# LEDBAKL_TPS61042.net
KiCad netlist of a schematic drawn in Altium Designer
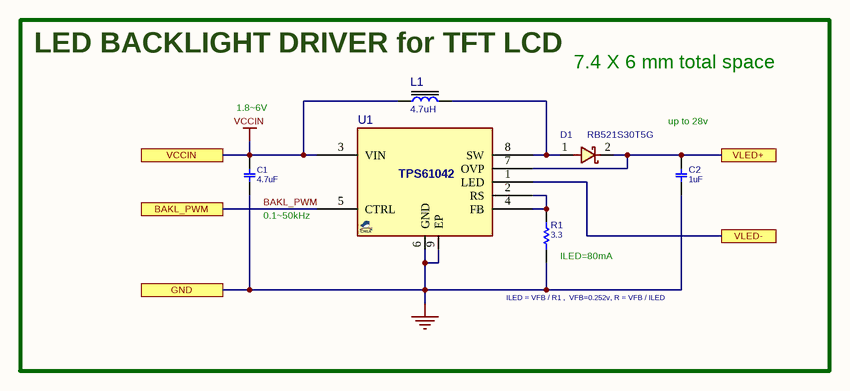
[diagram p0: LEDBAKL_TPS61042.SchDoc]

(export (version "E")
  (design (tool "Eeschema 10.0.6"))
  (components
    (comp (ref "C1")
      (value "4.7uF")
      (footprint "C0402")
      (description "CAP, MLCC")
      (fields (field (name "MANF_P#") "CL05A475MP5NRNC") (field (name "MANF") "Samsung"))
      (libsource (lib "passive_smd") (part "CAP_SMD_MLCC"))
    )
    (comp (ref "C2")
      (value "1uF")
      (footprint "C0603")
      (description "CAP, MLCC")
      (fields (field (name "MANF_P#") "CL10A105KB8NNNC") (field (name "MANF") "Samsung"))
      (libsource (lib "passive_smd") (part "CAP_SMD_MLCC"))
    )
    (comp (ref "D1")
      (value "RB521S30T5G")
      (footprint "D_SOD523")
      (description "DIODE, SCHOTTKY")
      (fields (field (name "MANF") "DIODES"))
      (libsource (lib "diode") (part "DIODE_SMD_SCHOTTKY_1N5819"))
    )
    (comp (ref "L1")
      (value "4.7uH")
      (footprint "L0603")
      (description "INDUCTOR, POWER, SMD")
      (fields (field (name "MANF_P#") "MLZ1608E4R7MT"))
      (libsource (lib "passive") (part "INDPWR_SMD"))
    )
    (comp (ref "R1")
      (value "3.3")
      (footprint "R0402")
      (description "RESISTOR, SMD, 20K, 0402")
      (fields (field (name "MANF") "Yageo") (field (name "MANF_P#") "RK73H1ETTP2002F"))
      (libsource (lib "chila_passive") (part "RES_SMD"))
    )
    (comp (ref "U1")
      (value "TPS61042")
      (footprint "SON65_8T_3030")
      (description "REG, Switching, Boost, 0.5A, ADJ, 1MHz")
      (fields (field (name "MANF_P#") "TPS61042DRB") (field (name "MANF") "TI"))
      (libsource (lib "pwr_switching_boost") (part "VREG_TPS61042_SON8"))
    )
  )
  (nets
    (net (code "1") (name "/BAKL_PWM") (class "Default")
      (node (ref "U1") (pin "5") (pinfunction "CTRL_5") (pintype "passive"))
    )
    (net (code "2") (name "/VLED+") (class "Default")
      (node (ref "C2") (pin "2") (pinfunction "2_2") (pintype "passive"))
      (node (ref "D1") (pin "2") (pinfunction "2_2") (pintype "passive"))
      (node (ref "U1") (pin "7") (pinfunction "OVP_7") (pintype "passive"))
    )
    (net (code "3") (name "/VLED-") (class "Default")
      (node (ref "U1") (pin "1") (pinfunction "LED_1") (pintype "passive"))
    )
    (net (code "4") (name "GND") (class "Default")
      (node (ref "C1") (pin "1") (pinfunction "1_1") (pintype "passive"))
      (node (ref "C2") (pin "1") (pinfunction "1_1") (pintype "passive"))
      (node (ref "R1") (pin "2") (pinfunction "2_2") (pintype "passive"))
      (node (ref "U1") (pin "6") (pinfunction "GND_6") (pintype "passive"))
      (node (ref "U1") (pin "9") (pinfunction "EP_9") (pintype "passive"))
    )
    (net (code "5") (name "Net-(U1-FB)") (class "Default")
      (node (ref "R1") (pin "1") (pinfunction "1_1") (pintype "passive"))
      (node (ref "U1") (pin "2") (pinfunction "RS_2") (pintype "passive"))
      (node (ref "U1") (pin "4") (pinfunction "FB_4") (pintype "passive"))
    )
    (net (code "6") (name "Net-(U1-SW)") (class "Default")
      (node (ref "D1") (pin "1") (pinfunction "1_1") (pintype "passive"))
      (node (ref "L1") (pin "2") (pinfunction "2_2") (pintype "passive"))
      (node (ref "U1") (pin "8") (pinfunction "SW_8") (pintype "passive"))
    )
    (net (code "7") (name "VCCIN") (class "Default")
      (node (ref "C1") (pin "2") (pinfunction "2_2") (pintype "passive"))
      (node (ref "L1") (pin "1") (pinfunction "1_1") (pintype "passive"))
      (node (ref "U1") (pin "3") (pinfunction "VIN_3") (pintype "passive"))
    )
  )
)
